# 4_MISC.net
KiCad netlist of a schematic drawn in Altium Designer
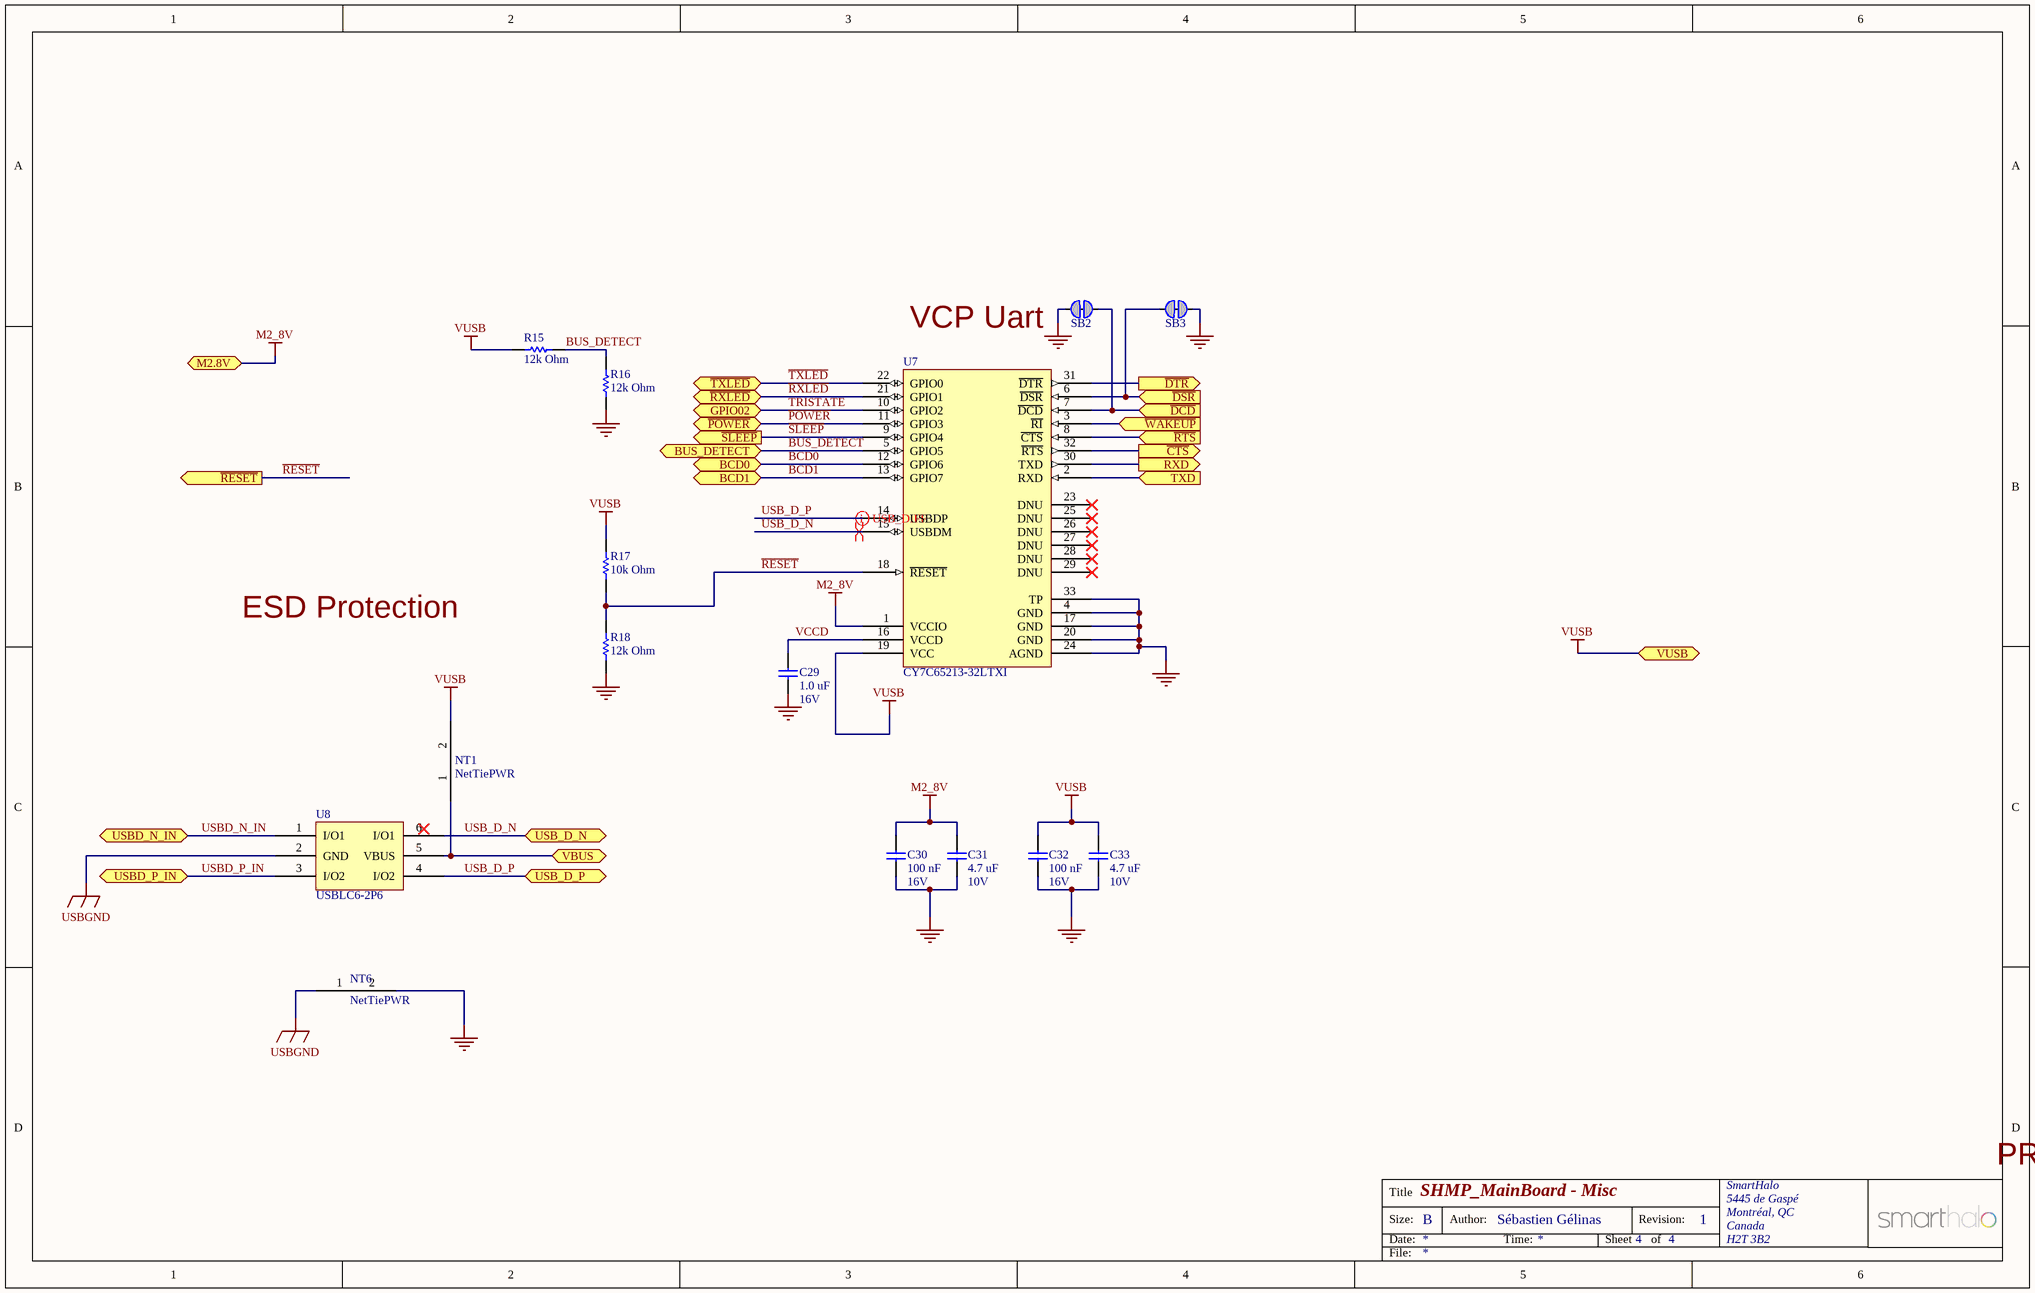
[diagram p0: 4_MISC.SchDoc]

(export (version "E")
  (design (tool "Eeschema 10.0.6"))
  (components
    (comp (ref "C29")
      (value "1.0 uF")
      (footprint "Varitron_CAP0603")
      (description "1.0 uF 16V X7R 10% 0603 (1608 Metric)  SMD")
      (fields (field (name "TOLERANCE") "10%") (field (name "VOLTAGE RATING") "16V"))
      (libsource (lib "SmartHalo") (part "Varitron_CAP0603"))
    )
    (comp (ref "C30")
      (value "100 nF")
      (footprint "Varitron_CAP0402")
      (description "100 nF 16V X7R 10% 0402 (1005 Metric)  SMD")
      (fields (field (name "TOLERANCE") "10%") (field (name "VOLTAGE RATING") "16V"))
      (libsource (lib "SmartHalo") (part "Varitron_CAP0402"))
    )
    (comp (ref "C31")
      (value "4.7 uF")
      (footprint "Varitron_CAP0603")
      (description "4.7 uF 10V X7R 10% 0603 (1608 Metric)  SMD")
      (fields (field (name "TOLERANCE") "10%") (field (name "VOLTAGE RATING") "10V"))
      (libsource (lib "SmartHalo") (part "Varitron_CAP0603"))
    )
    (comp (ref "C32")
      (value "100 nF")
      (footprint "Varitron_CAP0402")
      (description "100 nF 16V X7R 10% 0402 (1005 Metric)  SMD")
      (fields (field (name "TOLERANCE") "10%") (field (name "VOLTAGE RATING") "16V"))
      (libsource (lib "SmartHalo") (part "Varitron_CAP0402"))
    )
    (comp (ref "C33")
      (value "4.7 uF")
      (footprint "Varitron_CAP0603")
      (description "4.7 uF 10V X7R 10% 0603 (1608 Metric)  SMD")
      (fields (field (name "TOLERANCE") "10%") (field (name "VOLTAGE RATING") "10V"))
      (libsource (lib "SmartHalo") (part "Varitron_CAP0603"))
    )
    (comp (ref "NT1")
      (value "NetTiePWR")
      (footprint "NetTiePWR")
      (libsource (lib "SmartHalo") (part "NetTiePWR"))
    )
    (comp (ref "NT6")
      (value "NetTiePWR")
      (footprint "NetTiePWR")
      (libsource (lib "SmartHalo") (part "NetTiePWR"))
    )
    (comp (ref "R15")
      (value "12k Ohm")
      (footprint "Varitron_RES0402")
      (description "12k 0.063W 5%  0402 (1005 Metric)  SMD")
      (fields (field (name "TOLERANCE") "5%") (field (name "POWER") "0.063W"))
      (libsource (lib "SmartHalo") (part "Varitron_RES0402"))
    )
    (comp (ref "R16")
      (value "12k Ohm")
      (footprint "Varitron_RES0402")
      (description "12k 0.063W 5%  0402 (1005 Metric)  SMD")
      (fields (field (name "TOLERANCE") "5%") (field (name "POWER") "0.063W"))
      (libsource (lib "SmartHalo") (part "Varitron_RES0402"))
    )
    (comp (ref "R17")
      (value "10k Ohm")
      (footprint "Varitron_RES0402")
      (description "10k 0.063W 5%  0402 (1005 Metric)  SMD")
      (fields (field (name "TOLERANCE") "5%") (field (name "POWER") "0.063W"))
      (libsource (lib "SmartHalo") (part "Varitron_RES0402"))
    )
    (comp (ref "R18")
      (value "12k Ohm")
      (footprint "Varitron_RES0402")
      (description "12k 0.063W 5%  0402 (1005 Metric)  SMD")
      (fields (field (name "TOLERANCE") "5%") (field (name "POWER") "0.063W"))
      (libsource (lib "SmartHalo") (part "Varitron_RES0402"))
    )
    (comp (ref "SB2")
      (value "Solderbridge")
      (footprint "Solderbridge_Shorted")
      (description "Shorted Solderbridge")
      (libsource (lib "SmartHalo") (part "SOLDERBRIDGE_SHORTED"))
    )
    (comp (ref "SB3")
      (value "Solderbridge")
      (footprint "Solderbridge_Shorted")
      (description "Shorted Solderbridge")
      (libsource (lib "") (part "SOLDERBRIDGE_SHORTED_1"))
    )
    (comp (ref "U7")
      (value "CY7C65213-32LTXI")
      (footprint "QFN-32-TP")
      (description "IC USB TO UART BRIDGE 32QFN")
      (fields (field (name "MANUFACTURER") "Cypress"))
      (libsource (lib "SmartHalo") (part "CY7C65213-32LTXI"))
    )
    (comp (ref "U8")
      (value "USBLC6-2P6")
      (footprint "ST-SOT666")
      (description "Very low capacitance ESD protection")
      (fields (field (name "MANUFACTURER") "STMicroelectronics"))
      (libsource (lib "SmartHalo") (part "USBLC6-2P6"))
    )
  )
  (nets
    (net (code "1") (name "/BCD0") (class "Default")
      (node (ref "U7") (pin "12") (pinfunction "GPIO6_12") (pintype "bidirectional"))
    )
    (net (code "2") (name "/BCD1") (class "Default")
      (node (ref "U7") (pin "13") (pinfunction "GPIO7_13") (pintype "bidirectional"))
    )
    (net (code "3") (name "/BUS_DETECT") (class "Default")
      (node (ref "R15") (pin "1") (pinfunction "1_1") (pintype "passive"))
      (node (ref "R16") (pin "1") (pinfunction "1_1") (pintype "passive"))
      (node (ref "U7") (pin "5") (pinfunction "GPIO5_5") (pintype "bidirectional"))
    )
    (net (code "4") (name "/RXD") (class "Default")
      (node (ref "U7") (pin "30") (pinfunction "TXD_30") (pintype "output"))
    )
    (net (code "5") (name "/TRISTATE") (class "Default")
      (node (ref "U7") (pin "10") (pinfunction "GPIO2_10") (pintype "bidirectional"))
    )
    (net (code "6") (name "/TXD") (class "Default")
      (node (ref "U7") (pin "2") (pinfunction "RXD_2") (pintype "input"))
    )
    (net (code "7") (name "/USBD_N_IN") (class "Default")
      (node (ref "U8") (pin "1") (pinfunction "I/O1_1") (pintype "passive"))
    )
    (net (code "8") (name "/USBD_P_IN") (class "Default")
      (node (ref "U8") (pin "3") (pinfunction "I/O2_3") (pintype "passive"))
    )
    (net (code "9") (name "/USB_D_N") (class "Default")
      (node (ref "U7") (pin "15") (pinfunction "USBDM_15") (pintype "bidirectional"))
      (node (ref "U8") (pin "6") (pinfunction "I/O1_6") (pintype "passive"))
    )
    (net (code "10") (name "/USB_D_P") (class "Default")
      (node (ref "U7") (pin "14") (pinfunction "USBDP_14") (pintype "bidirectional"))
      (node (ref "U8") (pin "4") (pinfunction "I/O2_4") (pintype "passive"))
    )
    (net (code "11") (name "/VBUS") (class "Default")
      (node (ref "NT1") (pin "1") (pinfunction "NET1_1") (pintype "passive"))
      (node (ref "U8") (pin "5") (pinfunction "VBUS_5") (pintype "power_in"))
    )
    (net (code "12") (name "/VCCD") (class "Default")
      (node (ref "C29") (pin "1") (pinfunction "1_1") (pintype "passive"))
      (node (ref "U7") (pin "16") (pinfunction "VCCD_16") (pintype "power_in"))
    )
    (net (code "13") (name "/~{CTS}") (class "Default")
      (node (ref "U7") (pin "32") (pinfunction "~{RTS}_32") (pintype "output"))
    )
    (net (code "14") (name "/~{DCD}") (class "Default")
      (node (ref "SB2") (pin "2") (pinfunction "1_2") (pintype "passive"))
      (node (ref "U7") (pin "7") (pinfunction "~{DCD}_7") (pintype "input"))
    )
    (net (code "15") (name "/~{DSR}") (class "Default")
      (node (ref "SB3") (pin "2") (pinfunction "1_2") (pintype "passive"))
      (node (ref "U7") (pin "6") (pinfunction "~{DSR}_6") (pintype "input"))
    )
    (net (code "16") (name "/~{DTR}") (class "Default")
      (node (ref "U7") (pin "31") (pinfunction "~{DTR}_31") (pintype "output"))
    )
    (net (code "17") (name "/~{POWER}") (class "Default")
      (node (ref "U7") (pin "11") (pinfunction "GPIO3_11") (pintype "bidirectional"))
    )
    (net (code "18") (name "/~{RESET}") (class "Default")
      (node (ref "R17") (pin "1") (pinfunction "1_1") (pintype "passive"))
      (node (ref "R18") (pin "2") (pinfunction "2_2") (pintype "passive"))
      (node (ref "U7") (pin "18") (pinfunction "~{RESET}_18") (pintype "input"))
    )
    (net (code "19") (name "/~{RTS}") (class "Default")
      (node (ref "U7") (pin "8") (pinfunction "~{CTS}_8") (pintype "input"))
    )
    (net (code "20") (name "/~{RXLED}") (class "Default")
      (node (ref "U7") (pin "21") (pinfunction "GPIO1_21") (pintype "bidirectional"))
    )
    (net (code "21") (name "/~{SLEEP}") (class "Default")
      (node (ref "U7") (pin "9") (pinfunction "GPIO4_9") (pintype "bidirectional"))
    )
    (net (code "22") (name "/~{TXLED}") (class "Default")
      (node (ref "U7") (pin "22") (pinfunction "GPIO0_22") (pintype "bidirectional"))
    )
    (net (code "23") (name "/~{WAKEUP}") (class "Default")
      (node (ref "U7") (pin "3") (pinfunction "~{RI}_3") (pintype "input"))
    )
    (net (code "24") (name "GND") (class "Default")
      (node (ref "C29") (pin "2") (pinfunction "2_2") (pintype "passive"))
      (node (ref "C30") (pin "2") (pinfunction "2_2") (pintype "passive"))
      (node (ref "C31") (pin "2") (pinfunction "2_2") (pintype "passive"))
      (node (ref "C32") (pin "2") (pinfunction "2_2") (pintype "passive"))
      (node (ref "C33") (pin "2") (pinfunction "2_2") (pintype "passive"))
      (node (ref "NT6") (pin "2") (pinfunction "NET2_2") (pintype "passive"))
      (node (ref "R16") (pin "2") (pinfunction "2_2") (pintype "passive"))
      (node (ref "R18") (pin "1") (pinfunction "1_1") (pintype "passive"))
      (node (ref "SB2") (pin "1") (pinfunction "0_1") (pintype "passive"))
      (node (ref "SB3") (pin "1") (pinfunction "0_1") (pintype "passive"))
      (node (ref "U7") (pin "17") (pinfunction "GND_17") (pintype "power_in"))
      (node (ref "U7") (pin "20") (pinfunction "GND_20") (pintype "power_in"))
      (node (ref "U7") (pin "24") (pinfunction "AGND_24") (pintype "passive"))
      (node (ref "U7") (pin "33") (pinfunction "TP_33") (pintype "power_in"))
      (node (ref "U7") (pin "4") (pinfunction "GND_4") (pintype "power_in"))
    )
    (net (code "25") (name "M2_8V") (class "Default")
      (node (ref "C30") (pin "1") (pinfunction "1_1") (pintype "passive"))
      (node (ref "C31") (pin "1") (pinfunction "1_1") (pintype "passive"))
      (node (ref "U7") (pin "1") (pinfunction "VCCIO_1") (pintype "power_in"))
    )
    (net (code "26") (name "USBGND") (class "Default")
      (node (ref "NT6") (pin "1") (pinfunction "NET1_1") (pintype "passive"))
      (node (ref "U8") (pin "2") (pinfunction "GND_2") (pintype "power_in"))
    )
    (net (code "27") (name "VUSB") (class "Default")
      (node (ref "C32") (pin "1") (pinfunction "1_1") (pintype "passive"))
      (node (ref "C33") (pin "1") (pinfunction "1_1") (pintype "passive"))
      (node (ref "NT1") (pin "2") (pinfunction "NET2_2") (pintype "passive"))
      (node (ref "R15") (pin "2") (pinfunction "2_2") (pintype "passive"))
      (node (ref "R17") (pin "2") (pinfunction "2_2") (pintype "passive"))
      (node (ref "U7") (pin "19") (pinfunction "VCC_19") (pintype "power_in"))
    )
    (net (code "28") (name "unconnected-(U7-DNU-Pad23)") (class "Default")
      (node (ref "U7") (pin "23") (pinfunction "DNU_23") (pintype "passive+no_connect"))
    )
    (net (code "29") (name "unconnected-(U7-DNU-Pad25)") (class "Default")
      (node (ref "U7") (pin "25") (pinfunction "DNU_25") (pintype "passive+no_connect"))
    )
    (net (code "30") (name "unconnected-(U7-DNU-Pad26)") (class "Default")
      (node (ref "U7") (pin "26") (pinfunction "DNU_26") (pintype "passive+no_connect"))
    )
    (net (code "31") (name "unconnected-(U7-DNU-Pad27)") (class "Default")
      (node (ref "U7") (pin "27") (pinfunction "DNU_27") (pintype "passive+no_connect"))
    )
    (net (code "32") (name "unconnected-(U7-DNU-Pad28)") (class "Default")
      (node (ref "U7") (pin "28") (pinfunction "DNU_28") (pintype "passive+no_connect"))
    )
    (net (code "33") (name "unconnected-(U7-DNU-Pad29)") (class "Default")
      (node (ref "U7") (pin "29") (pinfunction "DNU_29") (pintype "passive+no_connect"))
    )
  )
)
